# Elavtor.net
KiCad netlist of a schematic drawn in Altium Designer
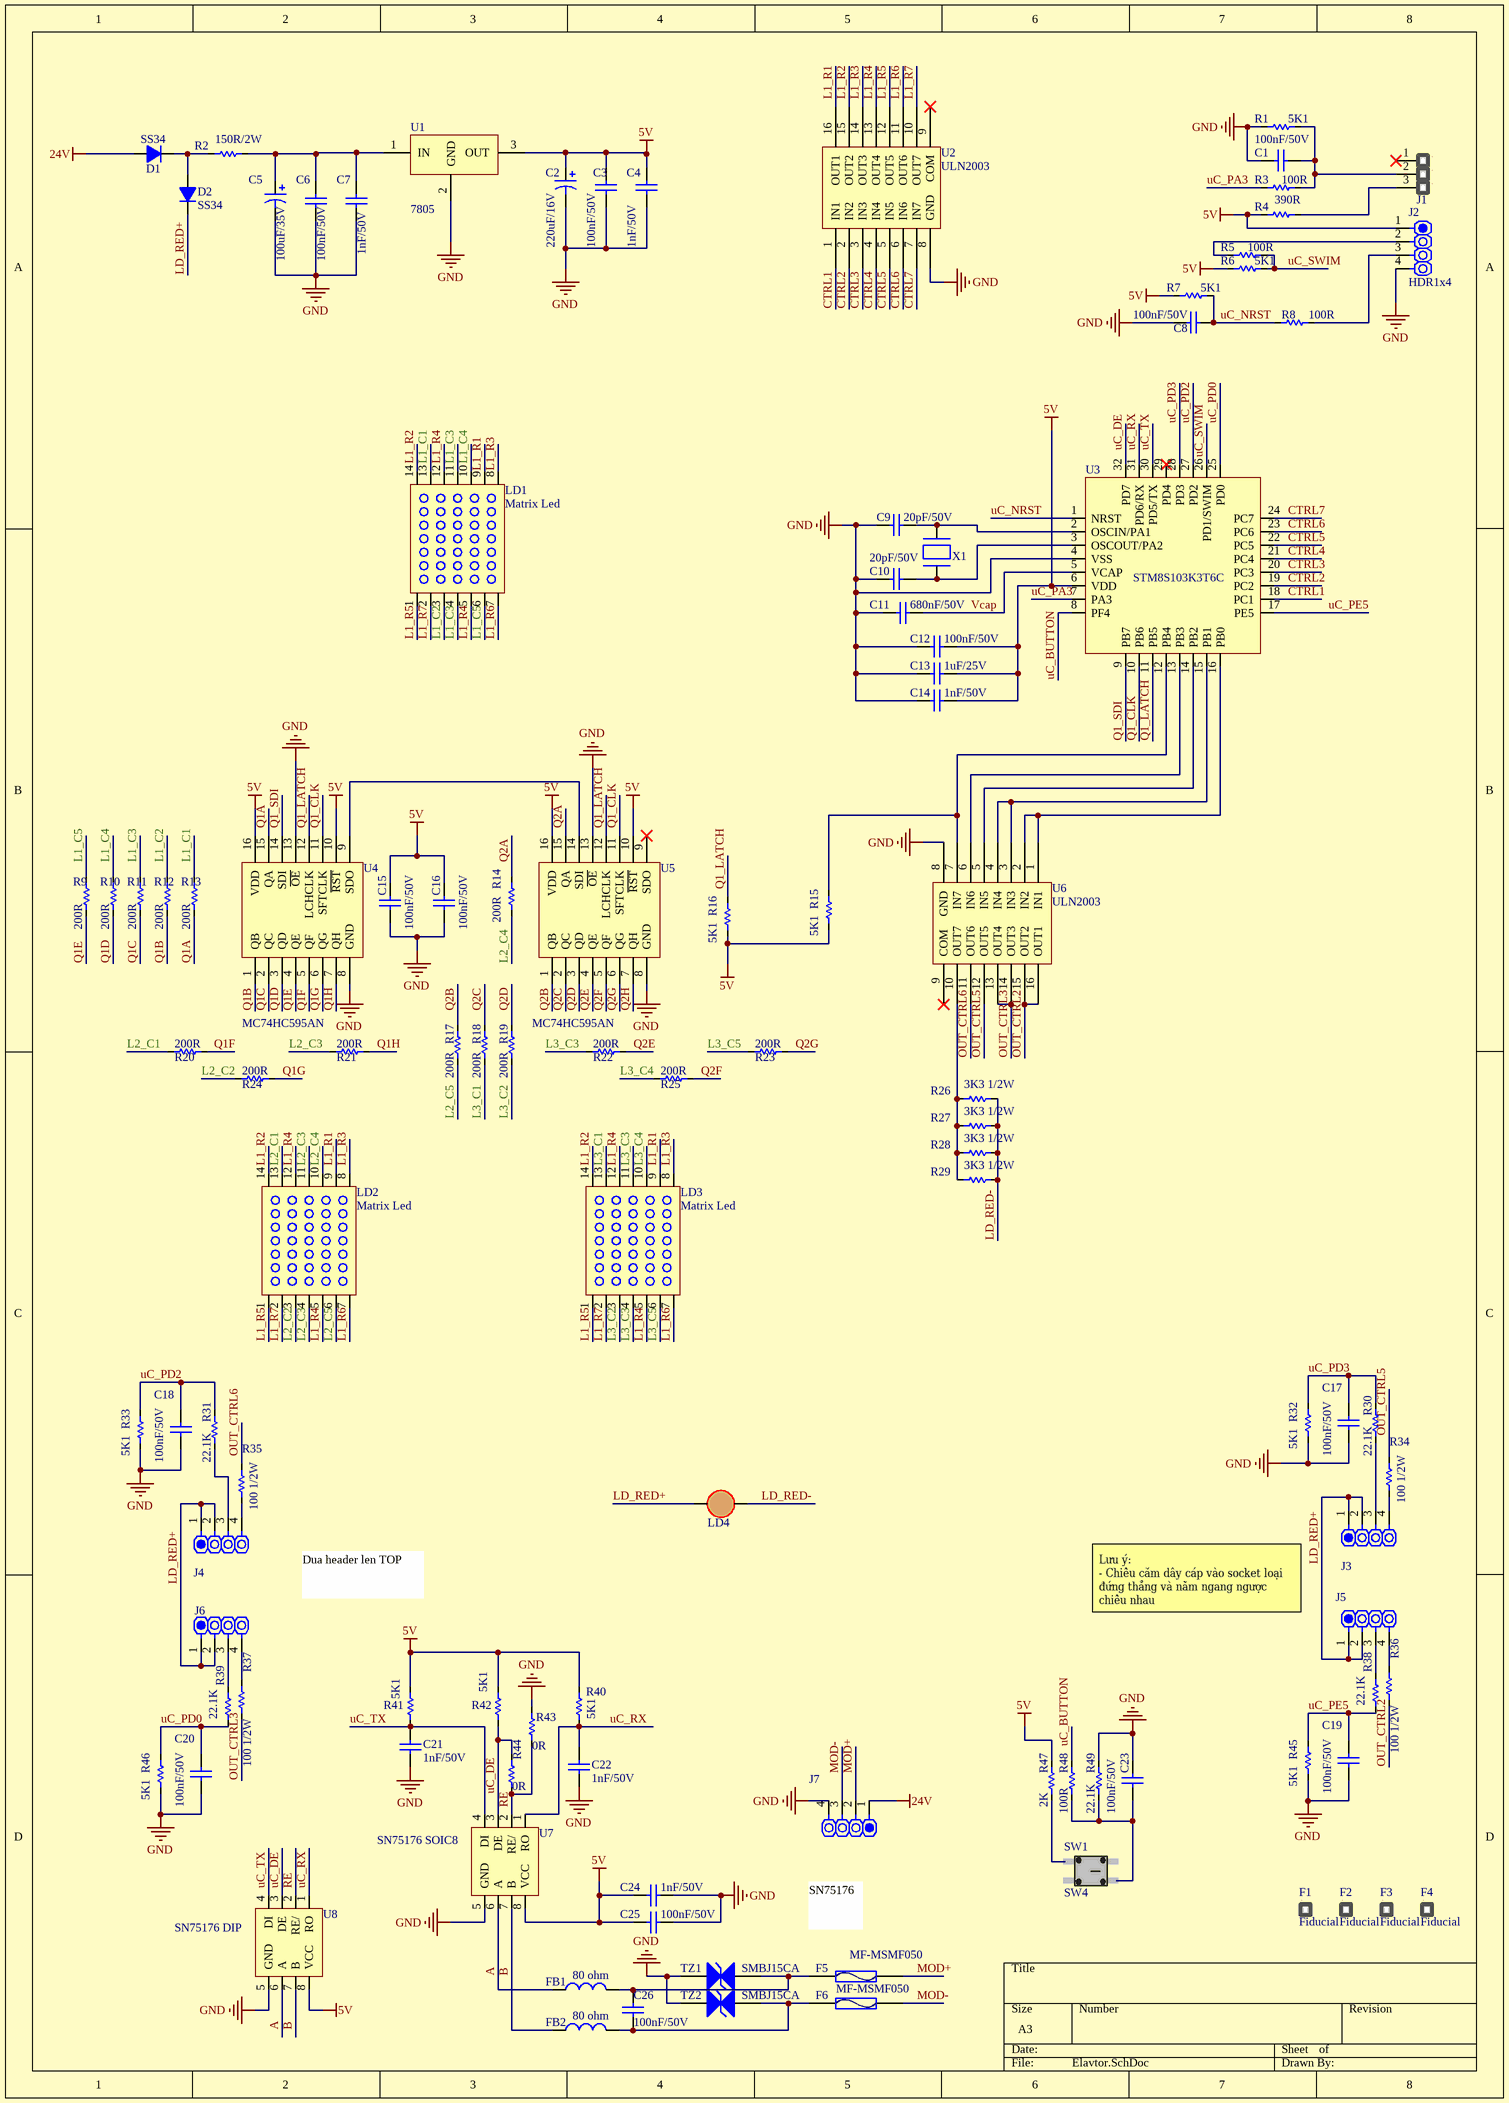
[diagram p0: Elavtor.SchDoc]

(export (version "E")
  (design (tool "Eeschema 10.0.6"))
  (components
    (comp (ref "C1")
      (value "100nF/50V")
      (footprint "FOOTPRINT_SMD:CAPC-0603-1608N")
      (description "CAP CER 100nF 50V 0603")
      (libsource (lib "SCHEMATIC") (part "Cap Ceramic"))
    )
    (comp (ref "C2")
      (value "220uF/16V")
      (footprint "FOOTPRINT_SMD:CAP.SMD_6.3MM")
      (description "Cap Pol 100uF 35V  SMD 6.3x7.7 mm")
      (fields (field (name "PUBLISHER") "Altium Limited"))
      (libsource (lib "SCHEMATIC") (part "Cap Pol 2mm"))
    )
    (comp (ref "C3")
      (value "100nF/50V")
      (footprint "FOOTPRINT_SMD:CAPC-0603-1608N")
      (description "CAP CER 100nF 50V 0603")
      (libsource (lib "SCHEMATIC") (part "Cap Ceramic"))
    )
    (comp (ref "C4")
      (value "1nF/50V")
      (footprint "FOOTPRINT_SMD:CAPC-0603-1608N")
      (description "CAP CER 1nF 50V 0603")
      (libsource (lib "SCHEMATIC") (part "Cap Ceramic"))
    )
    (comp (ref "C5")
      (value "100uF/35V")
      (footprint "FOOTPRINT_SMD:CAP.SMD_6.3MM")
      (description "Cap Pol 100uF 35V  SMD 6.3x7.7 mm")
      (fields (field (name "PUBLISHER") "Altium Limited"))
      (libsource (lib "SCHEMATIC") (part "Cap Pol 2mm"))
    )
    (comp (ref "C6")
      (value "100nF/50V")
      (footprint "FOOTPRINT_SMD:CAPC-0603-1608N")
      (description "CAP CER 100nF 50V 0603")
      (libsource (lib "SCHEMATIC") (part "Cap Ceramic"))
    )
    (comp (ref "C7")
      (value "1nF/50V")
      (footprint "FOOTPRINT_SMD:CAPC-0603-1608N")
      (description "CAP CER 1nF 50V 0603")
      (libsource (lib "SCHEMATIC") (part "Cap Ceramic"))
    )
    (comp (ref "C8")
      (value "100nF/50V")
      (footprint "FOOTPRINT_SMD:CAPC-0603-1608N")
      (description "CAP CER 100nF 50V 0603")
      (libsource (lib "SCHEMATIC") (part "Cap Ceramic"))
    )
    (comp (ref "C9")
      (value "20pF/50V")
      (footprint "FOOTPRINT_SMD:CAPC-0603-1608N")
      (description "CAP CER 20pF 50V 0603")
      (libsource (lib "SCHEMATIC") (part "Cap Ceramic"))
    )
    (comp (ref "C10")
      (value "20pF/50V")
      (footprint "FOOTPRINT_SMD:CAPC-0603-1608N")
      (description "CAP CER 20pF 50V 0603")
      (libsource (lib "SCHEMATIC") (part "Cap Ceramic"))
    )
    (comp (ref "C11")
      (value "680nF/50V")
      (footprint "FOOTPRINT_SMD:CAPC-0603-1608N")
      (description "CAP CER 680nF 50V 0603")
      (libsource (lib "SCHEMATIC") (part "Cap Ceramic"))
    )
    (comp (ref "C12")
      (value "100nF/50V")
      (footprint "FOOTPRINT_SMD:CAPC-0603-1608N")
      (description "CAP CER 100nF 50V 0603")
      (libsource (lib "SCHEMATIC") (part "Cap Ceramic"))
    )
    (comp (ref "C13")
      (value "1uF/25V")
      (footprint "FOOTPRINT_SMD:CAPC-0603-1608N")
      (description "CAP CER 1uF 25V 0603")
      (libsource (lib "SCHEMATIC") (part "Cap Ceramic"))
    )
    (comp (ref "C14")
      (value "1nF/50V")
      (footprint "FOOTPRINT_SMD:CAPC-0603-1608N")
      (description "CAP CER 1nF 50V 0603")
      (libsource (lib "SCHEMATIC") (part "Cap Ceramic"))
    )
    (comp (ref "C15")
      (value "100nF/50V")
      (footprint "FOOTPRINT_SMD:CAPC-0603-1608N")
      (description "CAP CER 100nF 50V 0603")
      (libsource (lib "SCHEMATIC") (part "Cap Ceramic"))
    )
    (comp (ref "C16")
      (value "100nF/50V")
      (footprint "FOOTPRINT_SMD:CAPC-0603-1608N")
      (description "CAP CER 100nF 50V 0603")
      (libsource (lib "SCHEMATIC") (part "Cap Ceramic"))
    )
    (comp (ref "C17")
      (value "100nF/50V")
      (footprint "FOOTPRINT_SMD:CAPC-0603-1608N")
      (description "CAP CER 100nF 50V 0603")
      (libsource (lib "SCHEMATIC") (part "Cap Ceramic"))
    )
    (comp (ref "C18")
      (value "100nF/50V")
      (footprint "FOOTPRINT_SMD:CAPC-0603-1608N")
      (description "CAP CER 100nF 50V 0603")
      (libsource (lib "SCHEMATIC") (part "Cap Ceramic"))
    )
    (comp (ref "C19")
      (value "100nF/50V")
      (footprint "FOOTPRINT_SMD:CAPC-0603-1608N")
      (description "CAP CER 100nF 50V 0603")
      (libsource (lib "SCHEMATIC") (part "Cap Ceramic"))
    )
    (comp (ref "C20")
      (value "100nF/50V")
      (footprint "FOOTPRINT_SMD:CAPC-0603-1608N")
      (description "CAP CER 100nF 50V 0603")
      (libsource (lib "SCHEMATIC") (part "Cap Ceramic"))
    )
    (comp (ref "C21")
      (value "1nF/50V")
      (footprint "FOOTPRINT_SMD:CAPC-0603-1608N")
      (description "CAP CER 1nF 50V 0805")
      (libsource (lib "SCHEMATIC") (part "Cap Ceramic"))
    )
    (comp (ref "C22")
      (value "1nF/50V")
      (footprint "FOOTPRINT_SMD:CAPC-0603-1608N")
      (description "CAP CER 1nF 50V 0603")
      (libsource (lib "SCHEMATIC") (part "Cap Ceramic"))
    )
    (comp (ref "C23")
      (value "100nF/50V")
      (footprint "FOOTPRINT_SMD:CAPC-0603-1608N")
      (description "CAP CER 100nF 50V 0603")
      (libsource (lib "SCHEMATIC") (part "Cap Ceramic"))
    )
    (comp (ref "C24")
      (value "1nF/50V")
      (footprint "FOOTPRINT_SMD:CAPC-0603-1608N")
      (description "CAP CER 1nF 50V 0603")
      (libsource (lib "SCHEMATIC") (part "Cap Ceramic"))
    )
    (comp (ref "C25")
      (value "100nF/50V")
      (footprint "FOOTPRINT_SMD:CAPC-0603-1608N")
      (description "CAP CER 100nF 50V 0603")
      (libsource (lib "SCHEMATIC") (part "Cap Ceramic"))
    )
    (comp (ref "C26")
      (value "100nF/50V")
      (footprint "FOOTPRINT_SMD:CAPC-0603-1608N")
      (description "CAP CER 100nF 50V 0603")
      (libsource (lib "SCHEMATIC") (part "Cap Ceramic"))
    )
    (comp (ref "D1")
      (value "SS34")
      (footprint "FOOTPRINT_SMD:DO-214AC,SMA")
      (description "SS34 SMA")
      (libsource (lib "SCHEMATIC") (part "Diode"))
    )
    (comp (ref "D2")
      (value "SS34")
      (footprint "FOOTPRINT_SMD:DO-214AC,SMA")
      (description "SS34 SMA")
      (libsource (lib "SCHEMATIC") (part "Diode"))
    )
    (comp (ref "F1")
      (value "Fiducial")
      (footprint "FOOTPRINT_SMD:Fiducial")
      (description "SMT Fiducial")
      (libsource (lib "SCHEMATIC") (part "Fiducial"))
    )
    (comp (ref "F2")
      (value "Fiducial")
      (footprint "FOOTPRINT_SMD:Fiducial")
      (description "SMT Fiducial")
      (libsource (lib "SCHEMATIC") (part "Fiducial"))
    )
    (comp (ref "F3")
      (value "Fiducial")
      (footprint "FOOTPRINT_SMD:Fiducial")
      (description "SMT Fiducial")
      (libsource (lib "SCHEMATIC") (part "Fiducial"))
    )
    (comp (ref "F4")
      (value "Fiducial")
      (footprint "FOOTPRINT_SMD:Fiducial")
      (description "SMT Fiducial")
      (libsource (lib "SCHEMATIC") (part "Fiducial"))
    )
    (comp (ref "F5")
      (value "MF-MSMF050")
      (footprint "FOOTPRINT_SMD:FUSE PTC 1812")
      (description "Surface Mount Fuse 1A/250V")
      (fields (field (name "MANUFACTURER") "Bourns Inc"))
      (libsource (lib "SCHEMATIC") (part "Fuse 1"))
    )
    (comp (ref "F6")
      (value "MF-MSMF050")
      (footprint "FOOTPRINT_SMD:FUSE PTC 1812")
      (description "Surface Mount Fuse 1A/250V")
      (fields (field (name "MANUFACTURER") "Bourns Inc"))
      (libsource (lib "SCHEMATIC") (part "Fuse 1"))
    )
    (comp (ref "FB1")
      (value "80 ohm")
      (footprint "L_0805")
      (description "Ferrite Bead 80 Ohm @100MHz nductor 0805")
      (libsource (lib "SCHEMATIC") (part "Inductor"))
    )
    (comp (ref "FB2")
      (value "80 ohm")
      (footprint "L_0805")
      (description "Ferrite Bead 80 Ohm @100MHz nductor 0805")
      (libsource (lib "SCHEMATIC") (part "Inductor"))
    )
    (comp (ref "J1")
      (value "HDR1x3")
      (footprint "FOOTPRINT_TH:HDR1X3")
      (description "2.54mm 3x1 Single Male Pin Header")
      (libsource (lib "SCHEMATIC") (part "HDR 1x3"))
    )
    (comp (ref "J2")
      (value "HDR1x4")
      (footprint "FOOTPRINT_TH:HDR1X4")
      (description "2.54mm 4x1 Single Male Pin Header")
      (fields (field (name "MANUFACTURER") "Taiwan") (field (name "PART NUMBER") "HEADER1X4"))
      (libsource (lib "SCHEMATIC") (part "HDR 1x4"))
    )
    (comp (ref "J3")
      (value "HDR1x4")
      (footprint "FOOTPRINT_TH:Hdr1x4 R Box")
      (description "5.08mm 4x1 Single Male RIght pin Header")
      (fields (field (name "MANUFACTURER") "Taiwan") (field (name "PART NUMBER") "HEADER1X4"))
      (libsource (lib "SCHEMATIC") (part "HDR 1x4"))
    )
    (comp (ref "J4")
      (value "HDR1x4")
      (footprint "FOOTPRINT_TH:Hdr1x4 R Box")
      (description "5.08mm 4x1 Single Male RIght pin Header")
      (fields (field (name "MANUFACTURER") "Taiwan") (field (name "PART NUMBER") "HEADER1X4"))
      (libsource (lib "SCHEMATIC") (part "HDR 1x4"))
    )
    (comp (ref "J5")
      (value "HDR1x4")
      (footprint "FOOTPRINT_TH:Hdr1x4 R Box")
      (description "5.08mm 4x1 Single Male RIght pin Header")
      (fields (field (name "MANUFACTURER") "Taiwan") (field (name "PART NUMBER") "HEADER1X4"))
      (libsource (lib "SCHEMATIC") (part "HDR 1x4"))
    )
    (comp (ref "J6")
      (value "HDR1x4")
      (footprint "FOOTPRINT_TH:Hdr1x4 R Box")
      (description "5.08mm 4x1 Single Male RIght pin Header")
      (fields (field (name "MANUFACTURER") "Taiwan") (field (name "PART NUMBER") "HEADER1X4"))
      (libsource (lib "SCHEMATIC") (part "HDR 1x4"))
    )
    (comp (ref "J7")
      (value "HDR1x4")
      (footprint "FOOTPRINT_TH:Hdr1x4 R Box")
      (description "5.08mm 4x1 Single Male RIght pin Header")
      (fields (field (name "MANUFACTURER") "Taiwan") (field (name "PART NUMBER") "HEADER1X4"))
      (libsource (lib "SCHEMATIC") (part "HDR 1x4"))
    )
    (comp (ref "LD1")
      (value "Matrix Led")
      (footprint "FOOTPRINT_TH:LED_Matrix 5*7")
      (description "Matrix Led 5x7")
      (libsource (lib "SCHEMATIC") (part "Matrix Led 5x7"))
    )
    (comp (ref "LD2")
      (value "Matrix Led")
      (footprint "FOOTPRINT_TH:LED_Matrix 5*7")
      (description "Matrix Led 5x7")
      (libsource (lib "SCHEMATIC") (part "Matrix Led 5x7"))
    )
    (comp (ref "LD3")
      (value "Matrix Led")
      (footprint "FOOTPRINT_TH:LED_Matrix 5*7")
      (description "Matrix Led 5x7")
      (libsource (lib "SCHEMATIC") (part "Matrix Led 5x7"))
    )
    (comp (ref "LD4")
      (value "LED TH 33x22 mm")
      (footprint "FOOTPRINT_TH:LED. 33x22 mm")
      (fields
        (field (name "MANUFACTURER") "Harvatek Technologies")
        (field (name "PART NUMBER") "HT17-2102SURC")
      )
      (libsource (lib "SCHEMATIC") (part "LED SINGLE"))
    )
    (comp (ref "R1")
      (value "5K1")
      (footprint "FOOTPRINT_SMD:R.SMD_0603")
      (description "RES SMD 5K1 OHM 5% 1/8W 0603")
      (fields (field (name "MANUFACTURER") "SUPEROHM") (field (name "PART NUMBER") "RR1608(0603)L102JT"))
      (libsource (lib "SCHEMATIC") (part "Resistor 1/4W"))
    )
    (comp (ref "R2")
      (value "150R/2W")
      (footprint "FOOTPRINT_TH:Resistor 1.5-2w")
      (description "RES SMD 150R OHM 5% 2W TH")
      (fields (field (name "MANUFACTURER") "SUPEROHM") (field (name "PART NUMBER") "RR1608(0603)L102JT"))
      (libsource (lib "SCHEMATIC") (part "Resistor 1/4W"))
    )
    (comp (ref "R3")
      (value "100R")
      (footprint "FOOTPRINT_SMD:R.SMD_0603")
      (description "RES SMD 100R OHM 1% 1/8W 0603")
      (fields (field (name "MANUFACTURER") "SUPEROHM") (field (name "PART NUMBER") "RR1608(0603)L102JT"))
      (libsource (lib "SCHEMATIC") (part "Resistor 1/4W"))
    )
    (comp (ref "R4")
      (value "390R")
      (footprint "FOOTPRINT_SMD:R.SMD_0603")
      (description "RES SMD 390R OHM 5% 1/8W 0603")
      (fields (field (name "MANUFACTURER") "SUPEROHM") (field (name "PART NUMBER") "RR1608(0603)L102JT"))
      (libsource (lib "SCHEMATIC") (part "Resistor 1/4W"))
    )
    (comp (ref "R5")
      (value "100R")
      (footprint "FOOTPRINT_SMD:R.SMD_0603")
      (description "RES SMD 100R OHM 1% 1/8W 0603")
      (fields (field (name "MANUFACTURER") "SUPEROHM") (field (name "PART NUMBER") "RR1608(0603)L102JT"))
      (libsource (lib "SCHEMATIC") (part "Resistor 1/4W"))
    )
    (comp (ref "R6")
      (value "5K1")
      (footprint "FOOTPRINT_SMD:R.SMD_0603")
      (description "RES SMD 5K1 OHM 5% 1/8W 0603")
      (fields (field (name "MANUFACTURER") "SUPEROHM") (field (name "PART NUMBER") "RR1608(0603)L102JT"))
      (libsource (lib "SCHEMATIC") (part "Resistor 1/4W"))
    )
    (comp (ref "R7")
      (value "5K1")
      (footprint "FOOTPRINT_SMD:R.SMD_0603")
      (description "RES SMD 5K1 OHM 5% 1/8W 0603")
      (fields (field (name "MANUFACTURER") "SUPEROHM") (field (name "PART NUMBER") "RR1608(0603)L102JT"))
      (libsource (lib "SCHEMATIC") (part "Resistor 1/4W"))
    )
    (comp (ref "R8")
      (value "100R")
      (footprint "FOOTPRINT_SMD:R.SMD_0603")
      (description "RES SMD 100R OHM 1% 1/10W 0603")
      (fields (field (name "MANUFACTURER") "SUPEROHM") (field (name "PART NUMBER") "RR1608(0603)L102JT"))
      (libsource (lib "SCHEMATIC") (part "Resistor 1/4W"))
    )
    (comp (ref "R9")
      (value "200R")
      (footprint "FOOTPRINT_SMD:R.SMD_0603")
      (description "RES SMD 200R OHM 5% 180W 0603")
      (fields (field (name "MANUFACTURER") "SUPEROHM") (field (name "PART NUMBER") "RR1608(0603)L102JT"))
      (libsource (lib "SCHEMATIC") (part "Resistor 1/4W"))
    )
    (comp (ref "R10")
      (value "200R")
      (footprint "FOOTPRINT_SMD:R.SMD_0603")
      (description "RES SMD 200R OHM 5% 180W 0603")
      (fields (field (name "MANUFACTURER") "SUPEROHM") (field (name "PART NUMBER") "RR1608(0603)L102JT"))
      (libsource (lib "SCHEMATIC") (part "Resistor 1/4W"))
    )
    (comp (ref "R11")
      (value "200R")
      (footprint "FOOTPRINT_SMD:R.SMD_0603")
      (description "RES SMD 200R OHM 5% 180W 0603")
      (fields (field (name "MANUFACTURER") "SUPEROHM") (field (name "PART NUMBER") "RR1608(0603)L102JT"))
      (libsource (lib "SCHEMATIC") (part "Resistor 1/4W"))
    )
    (comp (ref "R12")
      (value "200R")
      (footprint "FOOTPRINT_SMD:R.SMD_0603")
      (description "RES SMD 200R OHM 5% 180W 0603")
      (fields (field (name "MANUFACTURER") "SUPEROHM") (field (name "PART NUMBER") "RR1608(0603)L102JT"))
      (libsource (lib "SCHEMATIC") (part "Resistor 1/4W"))
    )
    (comp (ref "R13")
      (value "200R")
      (footprint "FOOTPRINT_SMD:R.SMD_0603")
      (description "RES SMD 200R OHM 5% 180W 0603")
      (fields (field (name "MANUFACTURER") "SUPEROHM") (field (name "PART NUMBER") "RR1608(0603)L102JT"))
      (libsource (lib "SCHEMATIC") (part "Resistor 1/4W"))
    )
    (comp (ref "R14")
      (value "200R")
      (footprint "FOOTPRINT_SMD:R.SMD_0603")
      (description "RES SMD 200R OHM 5% 180W 0603")
      (fields (field (name "MANUFACTURER") "SUPEROHM") (field (name "PART NUMBER") "RR1608(0603)L102JT"))
      (libsource (lib "SCHEMATIC") (part "Resistor 1/4W"))
    )
    (comp (ref "R15")
      (value "5K1")
      (footprint "FOOTPRINT_SMD:R.SMD_0603")
      (description "RES SMD 5K1 OHM 5% 1/8W 0603")
      (fields (field (name "MANUFACTURER") "SUPEROHM") (field (name "PART NUMBER") "RR1608(0603)L102JT"))
      (libsource (lib "SCHEMATIC") (part "Resistor 1/4W"))
    )
    (comp (ref "R16")
      (value "5K1")
      (footprint "FOOTPRINT_SMD:R.SMD_0603")
      (description "RES SMD 5K1 OHM 5% 1/8W 0603")
      (fields (field (name "MANUFACTURER") "SUPEROHM") (field (name "PART NUMBER") "RR1608(0603)L102JT"))
      (libsource (lib "SCHEMATIC") (part "Resistor 1/4W"))
    )
    (comp (ref "R17")
      (value "200R")
      (footprint "FOOTPRINT_SMD:R.SMD_0603")
      (description "RES SMD 200R OHM 5% 180W 0603")
      (fields (field (name "MANUFACTURER") "SUPEROHM") (field (name "PART NUMBER") "RR1608(0603)L102JT"))
      (libsource (lib "SCHEMATIC") (part "Resistor 1/4W"))
    )
    (comp (ref "R18")
      (value "200R")
      (footprint "FOOTPRINT_SMD:R.SMD_0603")
      (description "RES SMD 200R OHM 5% 180W 0603")
      (fields (field (name "MANUFACTURER") "SUPEROHM") (field (name "PART NUMBER") "RR1608(0603)L102JT"))
      (libsource (lib "SCHEMATIC") (part "Resistor 1/4W"))
    )
    (comp (ref "R19")
      (value "200R")
      (footprint "FOOTPRINT_SMD:R.SMD_0603")
      (description "RES SMD 200R OHM 5% 180W 0603")
      (fields (field (name "MANUFACTURER") "SUPEROHM") (field (name "PART NUMBER") "RR1608(0603)L102JT"))
      (libsource (lib "SCHEMATIC") (part "Resistor 1/4W"))
    )
    (comp (ref "R20")
      (value "200R")
      (footprint "FOOTPRINT_SMD:R.SMD_0603")
      (description "RES SMD 200R OHM 5% 180W 0603")
      (fields (field (name "MANUFACTURER") "SUPEROHM") (field (name "PART NUMBER") "RR1608(0603)L102JT"))
      (libsource (lib "SCHEMATIC") (part "Resistor 1/4W"))
    )
    (comp (ref "R21")
      (value "200R")
      (footprint "FOOTPRINT_SMD:R.SMD_0603")
      (description "RES SMD 200R OHM 5% 180W 0603")
      (fields (field (name "MANUFACTURER") "SUPEROHM") (field (name "PART NUMBER") "RR1608(0603)L102JT"))
      (libsource (lib "SCHEMATIC") (part "Resistor 1/4W"))
    )
    (comp (ref "R22")
      (value "200R")
      (footprint "FOOTPRINT_SMD:R.SMD_0603")
      (description "RES SMD 200R OHM 5% 180W 0603")
      (fields (field (name "MANUFACTURER") "SUPEROHM") (field (name "PART NUMBER") "RR1608(0603)L102JT"))
      (libsource (lib "SCHEMATIC") (part "Resistor 1/4W"))
    )
    (comp (ref "R23")
      (value "200R")
      (footprint "FOOTPRINT_SMD:R.SMD_0603")
      (description "RES SMD 200R OHM 5% 180W 0603")
      (fields (field (name "MANUFACTURER") "SUPEROHM") (field (name "PART NUMBER") "RR1608(0603)L102JT"))
      (libsource (lib "SCHEMATIC") (part "Resistor 1/4W"))
    )
    (comp (ref "R24")
      (value "200R")
      (footprint "FOOTPRINT_SMD:R.SMD_0603")
      (description "RES SMD 200R OHM 5% 180W 0603")
      (fields (field (name "MANUFACTURER") "SUPEROHM") (field (name "PART NUMBER") "RR1608(0603)L102JT"))
      (libsource (lib "SCHEMATIC") (part "Resistor 1/4W"))
    )
    (comp (ref "R25")
      (value "200R")
      (footprint "FOOTPRINT_SMD:R.SMD_0603")
      (description "RES SMD 200R OHM 5% 180W 0603")
      (fields (field (name "MANUFACTURER") "SUPEROHM") (field (name "PART NUMBER") "RR1608(0603)L102JT"))
      (libsource (lib "SCHEMATIC") (part "Resistor 1/4W"))
    )
    (comp (ref "R26")
      (value "3K3 1/2W")
      (footprint "FOOTPRINT_SMD:R.SMD_1210")
      (description "RES SMD 3K3 OHM 5% 1/2W 1210")
      (fields (field (name "MANUFACTURER") "SUPEROHM") (field (name "PART NUMBER") "RR1608(0603)L102JT"))
      (libsource (lib "SCHEMATIC") (part "Resistor 1/4W"))
    )
    (comp (ref "R27")
      (value "3K3 1/2W")
      (footprint "FOOTPRINT_SMD:R.SMD_1210")
      (description "RES SMD 3K3 OHM 5% 1/2W 1210")
      (fields (field (name "MANUFACTURER") "SUPEROHM") (field (name "PART NUMBER") "RR1608(0603)L102JT"))
      (libsource (lib "SCHEMATIC") (part "Resistor 1/4W"))
    )
    (comp (ref "R28")
      (value "3K3 1/2W")
      (footprint "FOOTPRINT_SMD:R.SMD_1210")
      (description "RES SMD 3K3 OHM 5% 1/2W 1210")
      (fields (field (name "MANUFACTURER") "SUPEROHM") (field (name "PART NUMBER") "RR1608(0603)L102JT"))
      (libsource (lib "SCHEMATIC") (part "Resistor 1/4W"))
    )
    (comp (ref "R29")
      (value "3K3 1/2W")
      (footprint "FOOTPRINT_SMD:R.SMD_1210")
      (description "RES SMD 3K3 OHM 5% 1/2W 1210")
      (fields (field (name "MANUFACTURER") "SUPEROHM") (field (name "PART NUMBER") "RR1608(0603)L102JT"))
      (libsource (lib "SCHEMATIC") (part "Resistor 1/4W"))
    )
    (comp (ref "R30")
      (value "22.1K")
      (footprint "FOOTPRINT_SMD:R.SMD_0603")
      (description "RES SMD 22.1K OHM 5% 1/8W 0603")
      (fields (field (name "MANUFACTURER") "SUPEROHM") (field (name "PART NUMBER") "RR1608(0603)L102JT"))
      (libsource (lib "SCHEMATIC") (part "Resistor 1/4W"))
    )
    (comp (ref "R31")
      (value "22.1K")
      (footprint "FOOTPRINT_SMD:R.SMD_0603")
      (description "RES SMD 22.1K OHM 5% 1/8W 0603")
      (fields (field (name "MANUFACTURER") "SUPEROHM") (field (name "PART NUMBER") "RR1608(0603)L102JT"))
      (libsource (lib "SCHEMATIC") (part "Resistor 1/4W"))
    )
    (comp (ref "R32")
      (value "5K1")
      (footprint "FOOTPRINT_SMD:R.SMD_0603")
      (description "RES SMD 5K1 OHM 5% 1/8W 0603")
      (fields (field (name "MANUFACTURER") "SUPEROHM") (field (name "PART NUMBER") "RR1608(0603)L102JT"))
      (libsource (lib "SCHEMATIC") (part "Resistor 1/4W"))
    )
    (comp (ref "R33")
      (value "5K1")
      (footprint "FOOTPRINT_SMD:R.SMD_0603")
      (description "RES SMD 5K1 OHM 5% 1/8W 0603")
      (fields (field (name "MANUFACTURER") "SUPEROHM") (field (name "PART NUMBER") "RR1608(0603)L102JT"))
      (libsource (lib "SCHEMATIC") (part "Resistor 1/4W"))
    )
    (comp (ref "R34")
      (value "100 1/2W")
      (footprint "FOOTPRINT_SMD:R.SMD_1210")
      (description "RES SMD 100 OHM 5% 1/2W 1210")
      (fields (field (name "MANUFACTURER") "SUPEROHM") (field (name "PART NUMBER") "RR1608(0603)L102JT"))
      (libsource (lib "SCHEMATIC") (part "Resistor 1/4W"))
    )
    (comp (ref "R35")
      (value "100 1/2W")
      (footprint "FOOTPRINT_SMD:R.SMD_1210")
      (description "RES SMD 100 OHM 5% 1/2W 1210")
      (fields (field (name "MANUFACTURER") "SUPEROHM") (field (name "PART NUMBER") "RR1608(0603)L102JT"))
      (libsource (lib "SCHEMATIC") (part "Resistor 1/4W"))
    )
    (comp (ref "R36")
      (value "100 1/2W")
      (footprint "FOOTPRINT_SMD:R.SMD_1210")
      (description "RES SMD 100 OHM 5% 1/2W 1210")
      (fields (field (name "MANUFACTURER") "SUPEROHM") (field (name "PART NUMBER") "RR1608(0603)L102JT"))
      (libsource (lib "SCHEMATIC") (part "Resistor 1/4W"))
    )
    (comp (ref "R37")
      (value "100 1/2W")
      (footprint "FOOTPRINT_SMD:R.SMD_1210")
      (description "RES SMD 100 OHM 5% 1/2W 1210")
      (fields (field (name "MANUFACTURER") "SUPEROHM") (field (name "PART NUMBER") "RR1608(0603)L102JT"))
      (libsource (lib "SCHEMATIC") (part "Resistor 1/4W"))
    )
    (comp (ref "R38")
      (value "22.1K")
      (footprint "FOOTPRINT_SMD:R.SMD_0603")
      (description "RES SMD 22.1K OHM 5% 1/8W 0603")
      (fields (field (name "MANUFACTURER") "SUPEROHM") (field (name "PART NUMBER") "RR1608(0603)L102JT"))
      (libsource (lib "SCHEMATIC") (part "Resistor 1/4W"))
    )
    (comp (ref "R39")
      (value "22.1K")
      (footprint "FOOTPRINT_SMD:R.SMD_0603")
      (description "RES SMD 22.1K OHM 5% 1/8W 0603")
      (fields (field (name "MANUFACTURER") "SUPEROHM") (field (name "PART NUMBER") "RR1608(0603)L102JT"))
      (libsource (lib "SCHEMATIC") (part "Resistor 1/4W"))
    )
    (comp (ref "R40")
      (value "5K1")
      (footprint "FOOTPRINT_SMD:R.SMD_0603")
      (description "RES SMD 5K1 OHM 5% 1/8W 0603")
      (fields (field (name "MANUFACTURER") "SUPEROHM") (field (name "PART NUMBER") "RR1608(0603)L102JT"))
      (libsource (lib "SCHEMATIC") (part "Resistor 1/4W"))
    )
    (comp (ref "R41")
      (value "5K1")
      (footprint "FOOTPRINT_SMD:R.SMD_0603")
      (description "RES SMD 5K1 OHM 5% 1/8W 0603")
      (fields (field (name "MANUFACTURER") "SUPEROHM") (field (name "PART NUMBER") "RR1608(0603)L102JT"))
      (libsource (lib "SCHEMATIC") (part "Resistor 1/4W"))
    )
    (comp (ref "R42")
      (value "5K1")
      (footprint "FOOTPRINT_SMD:R.SMD_0603")
      (description "RES SMD 5K1 OHM 5% 1/8W 0603")
      (fields (field (name "MANUFACTURER") "SUPEROHM") (field (name "PART NUMBER") "RR1608(0603)L102JT"))
      (libsource (lib "SCHEMATIC") (part "Resistor 1/4W"))
    )
    (comp (ref "R43")
      (value "0R")
      (footprint "FOOTPRINT_SMD:R.SMD_0603")
      (description "RES SMD 0R OHM 1% 1/10W 0603")
      (fields (field (name "MANUFACTURER") "SUPEROHM") (field (name "PART NUMBER") "RR1608(0603)L102JT"))
      (libsource (lib "SCHEMATIC") (part "Resistor 1/4W"))
    )
    (comp (ref "R44")
      (value "0R")
      (footprint "FOOTPRINT_SMD:R.SMD_0603")
      (description "RES SMD 0R OHM 1% 1/10W 0603")
      (fields (field (name "MANUFACTURER") "SUPEROHM") (field (name "PART NUMBER") "RR1608(0603)L102JT"))
      (libsource (lib "SCHEMATIC") (part "Resistor 1/4W"))
    )
    (comp (ref "R45")
      (value "5K1")
      (footprint "FOOTPRINT_SMD:R.SMD_0603")
      (description "RES SMD 5K1 OHM 5% 1/8W 0603")
      (fields (field (name "MANUFACTURER") "SUPEROHM") (field (name "PART NUMBER") "RR1608(0603)L102JT"))
      (libsource (lib "SCHEMATIC") (part "Resistor 1/4W"))
    )
    (comp (ref "R46")
      (value "5K1")
      (footprint "FOOTPRINT_SMD:R.SMD_0603")
      (description "RES SMD 5K1 OHM 5% 1/8W 0603")
      (fields (field (name "MANUFACTURER") "SUPEROHM") (field (name "PART NUMBER") "RR1608(0603)L102JT"))
      (libsource (lib "SCHEMATIC") (part "Resistor 1/4W"))
    )
    (comp (ref "R47")
      (value "2K")
      (footprint "FOOTPRINT_SMD:R.SMD_0603")
      (description "RES SMD 2K OHM 5% 1/8W 0603")
      (fields (field (name "MANUFACTURER") "SUPEROHM") (field (name "PART NUMBER") "RR1608(0603)L102JT"))
      (libsource (lib "SCHEMATIC") (part "Resistor 1/4W"))
    )
    (comp (ref "R48")
      (value "100R")
      (footprint "FOOTPRINT_SMD:R.SMD_0603")
      (description "RES SMD 100R OHM 1% 1/10W 0603")
      (fields (field (name "MANUFACTURER") "SUPEROHM") (field (name "PART NUMBER") "RR1608(0603)L102JT"))
      (libsource (lib "SCHEMATIC") (part "Resistor 1/4W"))
    )
    (comp (ref "R49")
      (value "22.1K")
      (footprint "FOOTPRINT_SMD:R.SMD_0603")
      (description "RES SMD 22.1K OHM 5% 1/8W 0603")
      (fields (field (name "MANUFACTURER") "SUPEROHM") (field (name "PART NUMBER") "RR1608(0603)L102JT"))
      (libsource (lib "SCHEMATIC") (part "Resistor 1/4W"))
    )
    (comp (ref "SW1")
      (value "SW4")
      (footprint "FOOTPRINT_TH:SW4 SMALL")
      (description "Tact Switch 6x6x5 Black")
      (fields (field (name "PART NUMBER") "KAN0611-0501B"))
      (libsource (lib "SCHEMATIC") (part "SW4"))
    )
    (comp (ref "TZ1")
      (value "SMBJ15CA")
      (footprint "FOOTPRINT_SMD:DO-214AA,SMB")
      (fields (field (name "MANUFACTURER") "ON Semi"))
      (libsource (lib "Schematic") (part "TVS"))
    )
    (comp (ref "TZ2")
      (value "SMBJ15CA")
      (footprint "FOOTPRINT_SMD:DO-214AA,SMB")
      (fields (field (name "MANUFACTURER") "ON Semi"))
      (libsource (lib "Schematic") (part "TVS"))
    )
    (comp (ref "U1")
      (value "7805")
      (footprint "FOOTPRINT_SMD:TO-252")
      (description "LM7805 SMD TO-252")
      (libsource (lib "SCHEMATIC") (part "78XX"))
    )
    (comp (ref "U2")
      (value "ULN2003")
      (footprint "FOOTPRINT_SMD:SOIC16_150_N")
      (description "High-Current Darlington Transistor Arrays")
      (fields (field (name "MANUFACTURER") "Texas instruments"))
      (libsource (lib "") (part "ULN2003_1"))
    )
    (comp (ref "U3")
      (value "STM8S103K3T6C")
      (footprint "FOOTPRINT_SMD:LQFP32")
      (description "16 MHz STM8S 8-bit MCU, up to 8 Kbytes Flash, data\r\nEEPROM,10-bit ADC, 3 timers, UART, SPI, I²C")
      (libsource (lib "SCHEMATIC") (part "STM8S103K3T6C"))
    )
    (comp (ref "U4")
      (value "MC74HC595AN")
      (footprint "FOOTPRINT_SMD:SOIC16_150_N")
      (description "8-Bit Serial-Input/Serial or Prallel-Output Shift Register with Latched 3-State Outputs")
      (fields (field (name "PUBLISHER") "Altium Limited"))
      (libsource (lib "SCHEMATIC") (part "MC74HC595AN"))
    )
    (comp (ref "U5")
      (value "MC74HC595AN")
      (footprint "FOOTPRINT_SMD:SOIC16_150_N")
      (description "8-Bit Serial-Input/Serial or Prallel-Output Shift Register with Latched 3-State Outputs")
      (fields (field (name "PUBLISHER") "Altium Limited"))
      (libsource (lib "SCHEMATIC") (part "MC74HC595AN"))
    )
    (comp (ref "U6")
      (value "ULN2003")
      (footprint "FOOTPRINT_SMD:SOIC16_150_N")
      (description "High-Current Darlington Transistor Arrays")
      (fields (field (name "MANUFACTURER") "Texas instruments"))
      (libsource (lib "SCHEMATIC") (part "ULN2003"))
    )
    (comp (ref "U7")
      (value "SN75176 SOIC8")
      (footprint "FOOTPRINT_SMD:SOIC8 - JEDEC")
      (description "SN65HVD3082E")
      (fields (field (name "PART NUMBER") "SP485"))
      (libsource (lib "SCHEMATIC") (part "RS485"))
    )
    (comp (ref "U8")
      (value "SN75176 DIP")
      (footprint "FOOTPRINT_TH:DIP8/W0.3")
      (description "SOCKET DIP 8")
      (fields (field (name "PART NUMBER") "SP485"))
      (libsource (lib "SCHEMATIC") (part "RS485"))
    )
    (comp (ref "X1")
      (value "16MHz")
      (footprint "FOOTPRINT_TH:CRYSTAL")
      (description "CRYSTAL 16MHz 7PF SMD")
      (libsource (lib "SCHEMATIC") (part "CRYSTAL"))
    )
  )
  (nets
    (net (code "1") (name "/A") (class "Default")
      (node (ref "FB1") (pin "1") (pinfunction "1_1") (pintype "passive"))
      (node (ref "U7") (pin "6") (pinfunction "A_6") (pintype "passive"))
      (node (ref "U8") (pin "6") (pinfunction "A_6") (pintype "passive"))
    )
    (net (code "2") (name "/B") (class "Default")
      (node (ref "FB2") (pin "1") (pinfunction "1_1") (pintype "passive"))
      (node (ref "U7") (pin "7") (pinfunction "B_7") (pintype "passive"))
      (node (ref "U8") (pin "7") (pinfunction "B_7") (pintype "passive"))
    )
    (net (code "3") (name "/CTRL1") (class "Default")
      (node (ref "U2") (pin "1") (pinfunction "IN1_1") (pintype "passive"))
      (node (ref "U3") (pin "18") (pinfunction "PC1_18") (pintype "passive"))
    )
    (net (code "4") (name "/CTRL2") (class "Default")
      (node (ref "U2") (pin "2") (pinfunction "IN2_2") (pintype "passive"))
      (node (ref "U3") (pin "19") (pinfunction "PC2_19") (pintype "passive"))
    )
    (net (code "5") (name "/CTRL3") (class "Default")
      (node (ref "U2") (pin "3") (pinfunction "IN3_3") (pintype "passive"))
      (node (ref "U3") (pin "20") (pinfunction "PC3_20") (pintype "passive"))
    )
    (net (code "6") (name "/CTRL4") (class "Default")
      (node (ref "U2") (pin "4") (pinfunction "IN4_4") (pintype "passive"))
      (node (ref "U3") (pin "21") (pinfunction "PC4_21") (pintype "passive"))
    )
    (net (code "7") (name "/CTRL5") (class "Default")
      (node (ref "U2") (pin "5") (pinfunction "IN5_5") (pintype "passive"))
      (node (ref "U3") (pin "22") (pinfunction "PC5_22") (pintype "passive"))
    )
    (net (code "8") (name "/CTRL6") (class "Default")
      (node (ref "U2") (pin "6") (pinfunction "IN6_6") (pintype "passive"))
      (node (ref "U3") (pin "23") (pinfunction "PC6_23") (pintype "passive"))
    )
    (net (code "9") (name "/CTRL7") (class "Default")
      (node (ref "U2") (pin "7") (pinfunction "IN7_7") (pintype "passive"))
      (node (ref "U3") (pin "24") (pinfunction "PC7_24") (pintype "passive"))
    )
    (net (code "10") (name "/L1_C1") (class "Default")
      (node (ref "LD1") (pin "13") (pinfunction "13_13") (pintype "passive"))
      (node (ref "R13") (pin "2") (pinfunction "2_2") (pintype "passive"))
    )
    (net (code "11") (name "/L1_C2") (class "Default")
      (node (ref "LD1") (pin "3") (pinfunction "3_3") (pintype "passive"))
      (node (ref "R12") (pin "2") (pinfunction "2_2") (pintype "passive"))
    )
    (net (code "12") (name "/L1_C3") (class "Default")
      (node (ref "LD1") (pin "11") (pinfunction "11_11") (pintype "passive"))
      (node (ref "LD1") (pin "4") (pinfunction "4_4") (pintype "passive"))
      (node (ref "R11") (pin "2") (pinfunction "2_2") (pintype "passive"))
    )
    (net (code "13") (name "/L1_C4") (class "Default")
      (node (ref "LD1") (pin "10") (pinfunction "10_10") (pintype "passive"))
      (node (ref "R10") (pin "2") (pinfunction "2_2") (pintype "passive"))
    )
    (net (code "14") (name "/L1_C5") (class "Default")
      (node (ref "LD1") (pin "6") (pinfunction "6_6") (pintype "passive"))
      (node (ref "R9") (pin "2") (pinfunction "2_2") (pintype "passive"))
    )
    (net (code "15") (name "/L1_R1") (class "Default")
      (node (ref "LD1") (pin "9") (pinfunction "9_9") (pintype "passive"))
      (node (ref "LD2") (pin "9") (pinfunction "9_9") (pintype "passive"))
      (node (ref "LD3") (pin "9") (pinfunction "9_9") (pintype "passive"))
      (node (ref "U2") (pin "16") (pinfunction "OUT1_16") (pintype "passive"))
    )
    (net (code "16") (name "/L1_R2") (class "Default")
      (node (ref "LD1") (pin "14") (pinfunction "14_14") (pintype "passive"))
      (node (ref "LD2") (pin "14") (pinfunction "14_14") (pintype "passive"))
      (node (ref "LD3") (pin "14") (pinfunction "14_14") (pintype "passive"))
      (node (ref "U2") (pin "15") (pinfunction "OUT2_15") (pintype "passive"))
    )
    (net (code "17") (name "/L1_R3") (class "Default")
      (node (ref "LD1") (pin "8") (pinfunction "8_8") (pintype "passive"))
      (node (ref "LD2") (pin "8") (pinfunction "8_8") (pintype "passive"))
      (node (ref "LD3") (pin "8") (pinfunction "8_8") (pintype "passive"))
      (node (ref "U2") (pin "14") (pinfunction "OUT3_14") (pintype "passive"))
    )
    (net (code "18") (name "/L1_R4") (class "Default")
      (node (ref "LD1") (pin "12") (pinfunction "12_12") (pintype "passive"))
      (node (ref "LD1") (pin "5") (pinfunction "5_5") (pintype "passive"))
      (node (ref "LD2") (pin "12") (pinfunction "12_12") (pintype "passive"))
      (node (ref "LD2") (pin "5") (pinfunction "5_5") (pintype "passive"))
      (node (ref "LD3") (pin "12") (pinfunction "12_12") (pintype "passive"))
      (node (ref "LD3") (pin "5") (pinfunction "5_5") (pintype "passive"))
      (node (ref "U2") (pin "13") (pinfunction "OUT4_13") (pintype "passive"))
    )
    (net (code "19") (name "/L1_R5") (class "Default")
      (node (ref "LD1") (pin "1") (pinfunction "1_1") (pintype "passive"))
      (node (ref "LD2") (pin "1") (pinfunction "1_1") (pintype "passive"))
      (node (ref "LD3") (pin "1") (pinfunction "1_1") (pintype "passive"))
      (node (ref "U2") (pin "12") (pinfunction "OUT5_12") (pintype "passive"))
    )
    (net (code "20") (name "/L1_R6") (class "Default")
      (node (ref "LD1") (pin "7") (pinfunction "7_7") (pintype "passive"))
      (node (ref "LD2") (pin "7") (pinfunction "7_7") (pintype "passive"))
      (node (ref "LD3") (pin "7") (pinfunction "7_7") (pintype "passive"))
      (node (ref "U2") (pin "11") (pinfunction "OUT6_11") (pintype "passive"))
    )
    (net (code "21") (name "/L1_R7") (class "Default")
      (node (ref "LD1") (pin "2") (pinfunction "2_2") (pintype "passive"))
      (node (ref "LD2") (pin "2") (pinfunction "2_2") (pintype "passive"))
      (node (ref "LD3") (pin "2") (pinfunction "2_2") (pintype "passive"))
      (node (ref "U2") (pin "10") (pinfunction "OUT7_10") (pintype "passive"))
    )
    (net (code "22") (name "/L2_C1") (class "Default")
      (node (ref "LD2") (pin "13") (pinfunction "13_13") (pintype "passive"))
      (node (ref "R20") (pin "2") (pinfunction "2_2") (pintype "passive"))
    )
    (net (code "23") (name "/L2_C2") (class "Default")
      (node (ref "LD2") (pin "3") (pinfunction "3_3") (pintype "passive"))
      (node (ref "R24") (pin "2") (pinfunction "2_2") (pintype "passive"))
    )
    (net (code "24") (name "/L2_C3") (class "Default")
      (node (ref "LD2") (pin "11") (pinfunction "11_11") (pintype "passive"))
      (node (ref "LD2") (pin "4") (pinfunction "4_4") (pintype "passive"))
      (node (ref "R21") (pin "2") (pinfunction "2_2") (pintype "passive"))
    )
    (net (code "25") (name "/L2_C4") (class "Default")
      (node (ref "LD2") (pin "10") (pinfunction "10_10") (pintype "passive"))
      (node (ref "R14") (pin "1") (pinfunction "1_1") (pintype "passive"))
    )
    (net (code "26") (name "/L2_C5") (class "Default")
      (node (ref "LD2") (pin "6") (pinfunction "6_6") (pintype "passive"))
      (node (ref "R17") (pin "1") (pinfunction "1_1") (pintype "passive"))
    )
    (net (code "27") (name "/L3_C1") (class "Default")
      (node (ref "LD3") (pin "13") (pinfunction "13_13") (pintype "passive"))
      (node (ref "R18") (pin "1") (pinfunction "1_1") (pintype "passive"))
    )
    (net (code "28") (name "/L3_C2") (class "Default")
      (node (ref "LD3") (pin "3") (pinfunction "3_3") (pintype "passive"))
      (node (ref "R19") (pin "1") (pinfunction "1_1") (pintype "passive"))
    )
    (net (code "29") (name "/L3_C3") (class "Default")
      (node (ref "LD3") (pin "11") (pinfunction "11_11") (pintype "passive"))
      (node (ref "LD3") (pin "4") (pinfunction "4_4") (pintype "passive"))
      (node (ref "R22") (pin "2") (pinfunction "2_2") (pintype "passive"))
    )
    (net (code "30") (name "/L3_C4") (class "Default")
      (node (ref "LD3") (pin "10") (pinfunction "10_10") (pintype "passive"))
      (node (ref "R25") (pin "2") (pinfunction "2_2") (pintype "passive"))
    )
    (net (code "31") (name "/L3_C5") (class "Default")
      (node (ref "LD3") (pin "6") (pinfunction "6_6") (pintype "passive"))
      (node (ref "R23") (pin "2") (pinfunction "2_2") (pintype "passive"))
    )
    (net (code "32") (name "/LD_RED+") (class "Default")
      (node (ref "D2") (pin "2") (pinfunction "K_2") (pintype "passive"))
      (node (ref "J3") (pin "1") (pinfunction "1_1") (pintype "passive"))
      (node (ref "J3") (pin "2") (pinfunction "2_2") (pintype "passive"))
      (node (ref "J4") (pin "1") (pinfunction "1_1") (pintype "passive"))
      (node (ref "J4") (pin "2") (pinfunction "2_2") (pintype "passive"))
      (node (ref "J5") (pin "1") (pinfunction "1_1") (pintype "passive"))
      (node (ref "J5") (pin "2") (pinfunction "2_2") (pintype "passive"))
      (node (ref "J6") (pin "1") (pinfunction "1_1") (pintype "passive"))
      (node (ref "J6") (pin "2") (pinfunction "2_2") (pintype "passive"))
      (node (ref "LD4") (pin "1") (pinfunction "A_1") (pintype "passive"))
    )
    (net (code "33") (name "/LD_RED-") (class "Default")
      (node (ref "LD4") (pin "2") (pinfunction "K_2") (pintype "passive"))
      (node (ref "R26") (pin "2") (pinfunction "2_2") (pintype "passive"))
      (node (ref "R27") (pin "2") (pinfunction "2_2") (pintype "passive"))
      (node (ref "R28") (pin "2") (pinfunction "2_2") (pintype "passive"))
      (node (ref "R29") (pin "2") (pinfunction "2_2") (pintype "passive"))
    )
    (net (code "34") (name "/MOD+") (class "Default")
      (node (ref "F5") (pin "2") (pinfunction "2_2") (pintype "passive"))
      (node (ref "J7") (pin "2") (pinfunction "2_2") (pintype "passive"))
    )
    (net (code "35") (name "/MOD-") (class "Default")
      (node (ref "F6") (pin "2") (pinfunction "2_2") (pintype "passive"))
      (node (ref "J7") (pin "3") (pinfunction "3_3") (pintype "passive"))
    )
    (net (code "36") (name "/OUT_CTRL2") (class "Default")
      (node (ref "R36") (pin "1") (pinfunction "1_1") (pintype "passive"))
      (node (ref "U6") (pin "15") (pinfunction "OUT2_15") (pintype "passive"))
      (node (ref "U6") (pin "16") (pinfunction "OUT1_16") (pintype "passive"))
    )
    (net (code "37") (name "/OUT_CTRL3") (class "Default")
      (node (ref "R37") (pin "1") (pinfunction "1_1") (pintype "passive"))
      (node (ref "U6") (pin "13") (pinfunction "OUT4_13") (pintype "passive"))
      (node (ref "U6") (pin "14") (pinfunction "OUT3_14") (pintype "passive"))
    )
    (net (code "38") (name "/OUT_CTRL5") (class "Default")
      (node (ref "R34") (pin "2") (pinfunction "2_2") (pintype "passive"))
      (node (ref "U6") (pin "12") (pinfunction "OUT5_12") (pintype "passive"))
    )
    (net (code "39") (name "/OUT_CTRL6") (class "Default")
      (node (ref "R35") (pin "2") (pinfunction "2_2") (pintype "passive"))
      (node (ref "U6") (pin "11") (pinfunction "OUT6_11") (pintype "passive"))
    )
    (net (code "40") (name "/Q1A") (class "Default")
      (node (ref "R13") (pin "1") (pinfunction "1_1") (pintype "passive"))
      (node (ref "U4") (pin "15") (pinfunction "QA_15") (pintype "tri_state"))
    )
    (net (code "41") (name "/Q1B") (class "Default")
      (node (ref "R12") (pin "1") (pinfunction "1_1") (pintype "passive"))
      (node (ref "U4") (pin "1") (pinfunction "QB_1") (pintype "tri_state"))
    )
    (net (code "42") (name "/Q1C") (class "Default")
      (node (ref "R11") (pin "1") (pinfunction "1_1") (pintype "passive"))
      (node (ref "U4") (pin "2") (pinfunction "QC_2") (pintype "tri_state"))
    )
    (net (code "43") (name "/Q1D") (class "Default")
      (node (ref "R10") (pin "1") (pinfunction "1_1") (pintype "passive"))
      (node (ref "U4") (pin "3") (pinfunction "QD_3") (pintype "tri_state"))
    )
    (net (code "44") (name "/Q1E") (class "Default")
      (node (ref "R9") (pin "1") (pinfunction "1_1") (pintype "passive"))
      (node (ref "U4") (pin "4") (pinfunction "QE_4") (pintype "tri_state"))
    )
    (net (code "45") (name "/Q1F") (class "Default")
      (node (ref "R20") (pin "1") (pinfunction "1_1") (pintype "passive"))
      (node (ref "U4") (pin "5") (pinfunction "QF_5") (pintype "tri_state"))
    )
    (net (code "46") (name "/Q1G") (class "Default")
      (node (ref "R24") (pin "1") (pinfunction "1_1") (pintype "passive"))
      (node (ref "U4") (pin "6") (pinfunction "QG_6") (pintype "tri_state"))
    )
    (net (code "47") (name "/Q1H") (class "Default")
      (node (ref "R21") (pin "1") (pinfunction "1_1") (pintype "passive"))
      (node (ref "U4") (pin "7") (pinfunction "QH_7") (pintype "tri_state"))
    )
    (net (code "48") (name "/Q1_CLK") (class "Default")
      (node (ref "U3") (pin "10") (pinfunction "PB6_10") (pintype "passive"))
      (node (ref "U4") (pin "11") (pinfunction "SFTCLK_11") (pintype "passive"))
      (node (ref "U5") (pin "11") (pinfunction "SFTCLK_11") (pintype "passive"))
    )
    (net (code "49") (name "/Q1_LATCH") (class "Default")
      (node (ref "R16") (pin "1") (pinfunction "1_1") (pintype "passive"))
      (node (ref "U3") (pin "11") (pinfunction "PB5_11") (pintype "passive"))
      (node (ref "U4") (pin "12") (pinfunction "LCHCLK_12") (pintype "passive"))
      (node (ref "U5") (pin "12") (pinfunction "LCHCLK_12") (pintype "passive"))
    )
    (net (code "50") (name "/Q1_SDI") (class "Default")
      (node (ref "U3") (pin "9") (pinfunction "PB7_9") (pintype "passive"))
      (node (ref "U4") (pin "14") (pinfunction "SDI_14") (pintype "passive"))
    )
    (net (code "51") (name "/Q2A") (class "Default")
      (node (ref "R14") (pin "2") (pinfunction "2_2") (pintype "passive"))
      (node (ref "U5") (pin "15") (pinfunction "QA_15") (pintype "tri_state"))
    )
    (net (code "52") (name "/Q2B") (class "Default")
      (node (ref "R17") (pin "2") (pinfunction "2_2") (pintype "passive"))
      (node (ref "U5") (pin "1") (pinfunction "QB_1") (pintype "tri_state"))
    )
    (net (code "53") (name "/Q2C") (class "Default")
      (node (ref "R18") (pin "2") (pinfunction "2_2") (pintype "passive"))
      (node (ref "U5") (pin "2") (pinfunction "QC_2") (pintype "tri_state"))
    )
    (net (code "54") (name "/Q2D") (class "Default")
      (node (ref "R19") (pin "2") (pinfunction "2_2") (pintype "passive"))
      (node (ref "U5") (pin "3") (pinfunction "QD_3") (pintype "tri_state"))
    )
    (net (code "55") (name "/Q2E") (class "Default")
      (node (ref "R22") (pin "1") (pinfunction "1_1") (pintype "passive"))
      (node (ref "U5") (pin "4") (pinfunction "QE_4") (pintype "tri_state"))
    )
    (net (code "56") (name "/Q2F") (class "Default")
      (node (ref "R25") (pin "1") (pinfunction "1_1") (pintype "passive"))
      (node (ref "U5") (pin "5") (pinfunction "QF_5") (pintype "tri_state"))
    )
    (net (code "57") (name "/Q2G") (class "Default")
      (node (ref "R23") (pin "1") (pinfunction "1_1") (pintype "passive"))
      (node (ref "U5") (pin "6") (pinfunction "QG_6") (pintype "tri_state"))
    )
    (net (code "58") (name "/Q2H") (class "Default")
      (node (ref "U5") (pin "7") (pinfunction "QH_7") (pintype "tri_state"))
    )
    (net (code "59") (name "/RE") (class "Default")
      (node (ref "R43") (pin "2") (pinfunction "2_2") (pintype "passive"))
      (node (ref "R44") (pin "2") (pinfunction "2_2") (pintype "passive"))
      (node (ref "U7") (pin "2") (pinfunction "RE/_2") (pintype "passive"))
      (node (ref "U8") (pin "2") (pinfunction "RE/_2") (pintype "passive"))
    )
    (net (code "60") (name "/Vcap") (class "Default")
      (node (ref "C11") (pin "1") (pinfunction "1_1") (pintype "passive"))
      (node (ref "U3") (pin "5") (pinfunction "VCAP_5") (pintype "passive"))
    )
    (net (code "61") (name "/uC_BUTTON") (class "Default")
      (node (ref "R48") (pin "1") (pinfunction "1_1") (pintype "passive"))
      (node (ref "U3") (pin "8") (pinfunction "PF4_8") (pintype "passive"))
    )
    (net (code "62") (name "/uC_DE") (class "Default")
      (node (ref "R42") (pin "2") (pinfunction "2_2") (pintype "passive"))
      (node (ref "R44") (pin "1") (pinfunction "1_1") (pintype "passive"))
      (node (ref "U3") (pin "32") (pinfunction "PD7_32") (pintype "passive"))
      (node (ref "U7") (pin "3") (pinfunction "DE_3") (pintype "passive"))
      (node (ref "U8") (pin "3") (pinfunction "DE_3") (pintype "passive"))
    )
    (net (code "63") (name "/uC_NRST") (class "Default")
      (node (ref "C8") (pin "1") (pinfunction "1_1") (pintype "passive"))
      (node (ref "R7") (pin "2") (pinfunction "2_2") (pintype "passive"))
      (node (ref "R8") (pin "2") (pinfunction "2_2") (pintype "passive"))
      (node (ref "U3") (pin "1") (pinfunction "NRST_1") (pintype "passive"))
    )
    (net (code "64") (name "/uC_PA3") (class "Default")
      (node (ref "R3") (pin "2") (pinfunction "2_2") (pintype "passive"))
      (node (ref "U3") (pin "7") (pinfunction "PA3_7") (pintype "passive"))
    )
    (net (code "65") (name "/uC_PD0") (class "Default")
      (node (ref "C20") (pin "2") (pinfunction "2_2") (pintype "passive"))
      (node (ref "R39") (pin "2") (pinfunction "2_2") (pintype "passive"))
      (node (ref "R46") (pin "1") (pinfunction "1_1") (pintype "passive"))
      (node (ref "U3") (pin "25") (pinfunction "PD0_25") (pintype "passive"))
    )
    (net (code "66") (name "/uC_PD2") (class "Default")
      (node (ref "C18") (pin "2") (pinfunction "2_2") (pintype "passive"))
      (node (ref "R31") (pin "1") (pinfunction "1_1") (pintype "passive"))
      (node (ref "R33") (pin "1") (pinfunction "1_1") (pintype "passive"))
      (node (ref "U3") (pin "27") (pinfunction "PD2_27") (pintype "passive"))
    )
    (net (code "67") (name "/uC_PD3") (class "Default")
      (node (ref "C17") (pin "2") (pinfunction "2_2") (pintype "passive"))
      (node (ref "R30") (pin "1") (pinfunction "1_1") (pintype "passive"))
      (node (ref "R32") (pin "1") (pinfunction "1_1") (pintype "passive"))
      (node (ref "U3") (pin "28") (pinfunction "PD3_28") (pintype "passive"))
    )
    (net (code "68") (name "/uC_PE5") (class "Default")
      (node (ref "C19") (pin "2") (pinfunction "2_2") (pintype "passive"))
      (node (ref "R38") (pin "2") (pinfunction "2_2") (pintype "passive"))
      (node (ref "R45") (pin "1") (pinfunction "1_1") (pintype "passive"))
      (node (ref "U3") (pin "17") (pinfunction "PE5_17") (pintype "passive"))
    )
    (net (code "69") (name "/uC_RX") (class "Default")
      (node (ref "C22") (pin "2") (pinfunction "2_2") (pintype "passive"))
      (node (ref "R40") (pin "2") (pinfunction "2_2") (pintype "passive"))
      (node (ref "U3") (pin "31") (pinfunction "PD6/RX_31") (pintype "passive"))
      (node (ref "U7") (pin "1") (pinfunction "RO_1") (pintype "passive"))
      (node (ref "U8") (pin "1") (pinfunction "RO_1") (pintype "passive"))
    )
    (net (code "70") (name "/uC_SWIM") (class "Default")
      (node (ref "R5") (pin "1") (pinfunction "1_1") (pintype "passive"))
      (node (ref "R6") (pin "2") (pinfunction "2_2") (pintype "passive"))
      (node (ref "U3") (pin "26") (pinfunction "PD1/SWIM_26") (pintype "passive"))
    )
    (net (code "71") (name "/uC_TX") (class "Default")
      (node (ref "C21") (pin "2") (pinfunction "2_2") (pintype "passive"))
      (node (ref "R41") (pin "2") (pinfunction "2_2") (pintype "passive"))
      (node (ref "U3") (pin "30") (pinfunction "PD5/TX_30") (pintype "passive"))
      (node (ref "U7") (pin "4") (pinfunction "DI_4") (pintype "passive"))
      (node (ref "U8") (pin "4") (pinfunction "DI_4") (pintype "passive"))
    )
    (net (code "72") (name "5V") (class "Default")
      (node (ref "C12") (pin "2") (pinfunction "2_2") (pintype "passive"))
      (node (ref "C13") (pin "2") (pinfunction "2_2") (pintype "passive"))
      (node (ref "C14") (pin "2") (pinfunction "2_2") (pintype "passive"))
      (node (ref "C15") (pin "2") (pinfunction "2_2") (pintype "passive"))
      (node (ref "C16") (pin "2") (pinfunction "2_2") (pintype "passive"))
      (node (ref "C2") (pin "1") (pinfunction "+_1") (pintype "passive"))
      (node (ref "C24") (pin "1") (pinfunction "1_1") (pintype "passive"))
      (node (ref "C25") (pin "2") (pinfunction "2_2") (pintype "passive"))
      (node (ref "C3") (pin "2") (pinfunction "2_2") (pintype "passive"))
      (node (ref "C4") (pin "1") (pinfunction "1_1") (pintype "passive"))
      (node (ref "J2") (pin "1") (pinfunction "1_1") (pintype "passive"))
      (node (ref "R15") (pin "2") (pinfunction "2_2") (pintype "passive"))
      (node (ref "R16") (pin "2") (pinfunction "2_2") (pintype "passive"))
      (node (ref "R4") (pin "2") (pinfunction "2_2") (pintype "passive"))
      (node (ref "R40") (pin "1") (pinfunction "1_1") (pintype "passive"))
      (node (ref "R41") (pin "1") (pinfunction "1_1") (pintype "passive"))
      (node (ref "R42") (pin "1") (pinfunction "1_1") (pintype "passive"))
      (node (ref "R47") (pin "1") (pinfunction "1_1") (pintype "passive"))
      (node (ref "R6") (pin "1") (pinfunction "1_1") (pintype "passive"))
      (node (ref "R7") (pin "1") (pinfunction "1_1") (pintype "passive"))
      (node (ref "U1") (pin "3") (pinfunction "OUT_3") (pintype "passive"))
      (node (ref "U3") (pin "6") (pinfunction "VDD_6") (pintype "passive"))
      (node (ref "U4") (pin "10") (pinfunction "~{RST}_10") (pintype "passive"))
      (node (ref "U4") (pin "16") (pinfunction "VDD_16") (pintype "power_in"))
      (node (ref "U5") (pin "10") (pinfunction "~{RST}_10") (pintype "passive"))
      (node (ref "U5") (pin "16") (pinfunction "VDD_16") (pintype "power_in"))
      (node (ref "U7") (pin "8") (pinfunction "VCC_8") (pintype "passive"))
      (node (ref "U8") (pin "8") (pinfunction "VCC_8") (pintype "passive"))
    )
    (net (code "73") (name "24V") (class "Default")
      (node (ref "D1") (pin "1") (pinfunction "A_1") (pintype "passive"))
      (node (ref "J7") (pin "1") (pinfunction "1_1") (pintype "passive"))
    )
    (net (code "74") (name "GND") (class "Default")
      (node (ref "C1") (pin "2") (pinfunction "2_2") (pintype "passive"))
      (node (ref "C10") (pin "1") (pinfunction "1_1") (pintype "passive"))
      (node (ref "C11") (pin "2") (pinfunction "2_2") (pintype "passive"))
      (node (ref "C12") (pin "1") (pinfunction "1_1") (pintype "passive"))
      (node (ref "C13") (pin "1") (pinfunction "1_1") (pintype "passive"))
      (node (ref "C14") (pin "1") (pinfunction "1_1") (pintype "passive"))
      (node (ref "C15") (pin "1") (pinfunction "1_1") (pintype "passive"))
      (node (ref "C16") (pin "1") (pinfunction "1_1") (pintype "passive"))
      (node (ref "C17") (pin "1") (pinfunction "1_1") (pintype "passive"))
      (node (ref "C18") (pin "1") (pinfunction "1_1") (pintype "passive"))
      (node (ref "C19") (pin "1") (pinfunction "1_1") (pintype "passive"))
      (node (ref "C2") (pin "2") (pinfunction "-_2") (pintype "passive"))
      (node (ref "C20") (pin "1") (pinfunction "1_1") (pintype "passive"))
      (node (ref "C21") (pin "1") (pinfunction "1_1") (pintype "passive"))
      (node (ref "C22") (pin "1") (pinfunction "1_1") (pintype "passive"))
      (node (ref "C23") (pin "2") (pinfunction "2_2") (pintype "passive"))
      (node (ref "C24") (pin "2") (pinfunction "2_2") (pintype "passive"))
      (node (ref "C25") (pin "1") (pinfunction "1_1") (pintype "passive"))
      (node (ref "C3") (pin "1") (pinfunction "1_1") (pintype "passive"))
      (node (ref "C4") (pin "2") (pinfunction "2_2") (pintype "passive"))
      (node (ref "C5") (pin "2") (pinfunction "-_2") (pintype "passive"))
      (node (ref "C6") (pin "1") (pinfunction "1_1") (pintype "passive"))
      (node (ref "C7") (pin "2") (pinfunction "2_2") (pintype "passive"))
      (node (ref "C8") (pin "2") (pinfunction "2_2") (pintype "passive"))
      (node (ref "C9") (pin "1") (pinfunction "1_1") (pintype "passive"))
      (node (ref "J2") (pin "4") (pinfunction "4_4") (pintype "passive"))
      (node (ref "J7") (pin "4") (pinfunction "4_4") (pintype "passive"))
      (node (ref "R1") (pin "1") (pinfunction "1_1") (pintype "passive"))
      (node (ref "R32") (pin "2") (pinfunction "2_2") (pintype "passive"))
      (node (ref "R33") (pin "2") (pinfunction "2_2") (pintype "passive"))
      (node (ref "R43") (pin "1") (pinfunction "1_1") (pintype "passive"))
      (node (ref "R45") (pin "2") (pinfunction "2_2") (pintype "passive"))
      (node (ref "R46") (pin "2") (pinfunction "2_2") (pintype "passive"))
      (node (ref "R49") (pin "1") (pinfunction "1_1") (pintype "passive"))
      (node (ref "TZ1") (pin "2") (pinfunction "2_2") (pintype "passive"))
      (node (ref "TZ2") (pin "2") (pinfunction "2_2") (pintype "passive"))
      (node (ref "U1") (pin "2") (pinfunction "GND_2") (pintype "passive"))
      (node (ref "U2") (pin "8") (pinfunction "GND_8") (pintype "passive"))
      (node (ref "U3") (pin "4") (pinfunction "VSS_4") (pintype "passive"))
      (node (ref "U4") (pin "13") (pinfunction "~{OE}_13") (pintype "passive"))
      (node (ref "U4") (pin "8") (pinfunction "GND_8") (pintype "power_in"))
      (node (ref "U5") (pin "13") (pinfunction "~{OE}_13") (pintype "passive"))
      (node (ref "U5") (pin "8") (pinfunction "GND_8") (pintype "power_in"))
      (node (ref "U6") (pin "8") (pinfunction "GND_8") (pintype "passive"))
      (node (ref "U7") (pin "5") (pinfunction "GND_5") (pintype "passive"))
      (node (ref "U8") (pin "5") (pinfunction "GND_5") (pintype "passive"))
    )
    (net (code "75") (name "Net-(C1-Pad1)") (class "Default")
      (node (ref "C1") (pin "1") (pinfunction "1_1") (pintype "passive"))
      (node (ref "J1") (pin "2") (pinfunction "2_2") (pintype "passive"))
      (node (ref "R1") (pin "2") (pinfunction "2_2") (pintype "passive"))
      (node (ref "R3") (pin "1") (pinfunction "1_1") (pintype "passive"))
    )
    (net (code "76") (name "Net-(C5-+)") (class "Default")
      (node (ref "C5") (pin "1") (pinfunction "+_1") (pintype "passive"))
      (node (ref "C6") (pin "2") (pinfunction "2_2") (pintype "passive"))
      (node (ref "C7") (pin "1") (pinfunction "1_1") (pintype "passive"))
      (node (ref "R2") (pin "2") (pinfunction "2_2") (pintype "passive"))
      (node (ref "U1") (pin "1") (pinfunction "IN_1") (pintype "passive"))
    )
    (net (code "77") (name "Net-(C23-Pad1)") (class "Default")
      (node (ref "C23") (pin "1") (pinfunction "1_1") (pintype "passive"))
      (node (ref "R48") (pin "2") (pinfunction "2_2") (pintype "passive"))
      (node (ref "R49") (pin "2") (pinfunction "2_2") (pintype "passive"))
      (node (ref "SW1") (pin "2") (pinfunction "2_2") (pintype "passive"))
    )
    (net (code "78") (name "Net-(C26-Pad1)") (class "Default")
      (node (ref "C26") (pin "1") (pinfunction "1_1") (pintype "passive"))
      (node (ref "F5") (pin "1") (pinfunction "1_1") (pintype "passive"))
      (node (ref "FB1") (pin "2") (pinfunction "2_2") (pintype "passive"))
      (node (ref "TZ1") (pin "1") (pinfunction "1_1") (pintype "passive"))
    )
    (net (code "79") (name "Net-(C26-Pad2)") (class "Default")
      (node (ref "C26") (pin "2") (pinfunction "2_2") (pintype "passive"))
      (node (ref "F6") (pin "1") (pinfunction "1_1") (pintype "passive"))
      (node (ref "FB2") (pin "2") (pinfunction "2_2") (pintype "passive"))
      (node (ref "TZ2") (pin "1") (pinfunction "1_1") (pintype "passive"))
    )
    (net (code "80") (name "Net-(D1-K)") (class "Default")
      (node (ref "D1") (pin "2") (pinfunction "K_2") (pintype "passive"))
      (node (ref "D2") (pin "1") (pinfunction "A_1") (pintype "passive"))
      (node (ref "R2") (pin "1") (pinfunction "1_1") (pintype "passive"))
    )
    (net (code "81") (name "Net-(J1-Pad3)") (class "Default")
      (node (ref "J1") (pin "3") (pinfunction "3_3") (pintype "passive"))
      (node (ref "R4") (pin "1") (pinfunction "1_1") (pintype "passive"))
    )
    (net (code "82") (name "Net-(J2-Pad2)") (class "Default")
      (node (ref "J2") (pin "2") (pinfunction "2_2") (pintype "passive"))
      (node (ref "R5") (pin "2") (pinfunction "2_2") (pintype "passive"))
    )
    (net (code "83") (name "Net-(J2-Pad3)") (class "Default")
      (node (ref "J2") (pin "3") (pinfunction "3_3") (pintype "passive"))
      (node (ref "R8") (pin "1") (pinfunction "1_1") (pintype "passive"))
    )
    (net (code "84") (name "Net-(J3-Pad3)") (class "Default")
      (node (ref "J3") (pin "3") (pinfunction "3_3") (pintype "passive"))
      (node (ref "R30") (pin "2") (pinfunction "2_2") (pintype "passive"))
    )
    (net (code "85") (name "Net-(J3-Pad4)") (class "Default")
      (node (ref "J3") (pin "4") (pinfunction "4_4") (pintype "passive"))
      (node (ref "R34") (pin "1") (pinfunction "1_1") (pintype "passive"))
    )
    (net (code "86") (name "Net-(J4-Pad3)") (class "Default")
      (node (ref "J4") (pin "3") (pinfunction "3_3") (pintype "passive"))
      (node (ref "R31") (pin "2") (pinfunction "2_2") (pintype "passive"))
    )
    (net (code "87") (name "Net-(J4-Pad4)") (class "Default")
      (node (ref "J4") (pin "4") (pinfunction "4_4") (pintype "passive"))
      (node (ref "R35") (pin "1") (pinfunction "1_1") (pintype "passive"))
    )
    (net (code "88") (name "Net-(J5-Pad3)") (class "Default")
      (node (ref "J5") (pin "3") (pinfunction "3_3") (pintype "passive"))
      (node (ref "R38") (pin "1") (pinfunction "1_1") (pintype "passive"))
    )
    (net (code "89") (name "Net-(J5-Pad4)") (class "Default")
      (node (ref "J5") (pin "4") (pinfunction "4_4") (pintype "passive"))
      (node (ref "R36") (pin "2") (pinfunction "2_2") (pintype "passive"))
    )
    (net (code "90") (name "Net-(J6-Pad3)") (class "Default")
      (node (ref "J6") (pin "3") (pinfunction "3_3") (pintype "passive"))
      (node (ref "R39") (pin "1") (pinfunction "1_1") (pintype "passive"))
    )
    (net (code "91") (name "Net-(J6-Pad4)") (class "Default")
      (node (ref "J6") (pin "4") (pinfunction "4_4") (pintype "passive"))
      (node (ref "R37") (pin "2") (pinfunction "2_2") (pintype "passive"))
    )
    (net (code "92") (name "Net-(R47-Pad2)") (class "Default")
      (node (ref "R47") (pin "2") (pinfunction "2_2") (pintype "passive"))
      (node (ref "SW1") (pin "4") (pinfunction "4_4") (pintype "passive"))
    )
    (net (code "93") (name "Net-(U3-OSCIN{slash}PA1)") (class "Default")
      (node (ref "C9") (pin "2") (pinfunction "2_2") (pintype "passive"))
      (node (ref "U3") (pin "2") (pinfunction "OSCIN/PA1_2") (pintype "passive"))
      (node (ref "X1") (pin "2") (pinfunction "2_2") (pintype "passive"))
    )
    (net (code "94") (name "Net-(U3-OSCOUT{slash}PA2)") (class "Default")
      (node (ref "C10") (pin "2") (pinfunction "2_2") (pintype "passive"))
      (node (ref "U3") (pin "3") (pinfunction "OSCOUT/PA2_3") (pintype "passive"))
      (node (ref "X1") (pin "1") (pinfunction "1_1") (pintype "passive"))
    )
    (net (code "95") (name "Net-(U3-PB0)") (class "Default")
      (node (ref "U3") (pin "16") (pinfunction "PB0_16") (pintype "passive"))
      (node (ref "U6") (pin "1") (pinfunction "IN1_1") (pintype "passive"))
      (node (ref "U6") (pin "2") (pinfunction "IN2_2") (pintype "passive"))
    )
    (net (code "96") (name "Net-(U3-PB1)") (class "Default")
      (node (ref "U3") (pin "15") (pinfunction "PB1_15") (pintype "passive"))
      (node (ref "U6") (pin "3") (pinfunction "IN3_3") (pintype "passive"))
      (node (ref "U6") (pin "4") (pinfunction "IN4_4") (pintype "passive"))
    )
    (net (code "97") (name "Net-(U3-PB2)") (class "Default")
      (node (ref "U3") (pin "14") (pinfunction "PB2_14") (pintype "passive"))
      (node (ref "U6") (pin "5") (pinfunction "IN5_5") (pintype "passive"))
    )
    (net (code "98") (name "Net-(U3-PB3)") (class "Default")
      (node (ref "U3") (pin "13") (pinfunction "PB3_13") (pintype "passive"))
      (node (ref "U6") (pin "6") (pinfunction "IN6_6") (pintype "passive"))
    )
    (net (code "99") (name "Net-(U3-PB4)") (class "Default")
      (node (ref "R15") (pin "1") (pinfunction "1_1") (pintype "passive"))
      (node (ref "U3") (pin "12") (pinfunction "PB4_12") (pintype "passive"))
      (node (ref "U6") (pin "7") (pinfunction "IN7_7") (pintype "passive"))
    )
    (net (code "100") (name "Net-(U4-SDO)") (class "Default")
      (node (ref "U4") (pin "9") (pinfunction "SDO_9") (pintype "passive"))
      (node (ref "U5") (pin "14") (pinfunction "SDI_14") (pintype "passive"))
    )
    (net (code "101") (name "Net-(U6-OUT7)") (class "Default")
      (node (ref "R26") (pin "1") (pinfunction "1_1") (pintype "passive"))
      (node (ref "R27") (pin "1") (pinfunction "1_1") (pintype "passive"))
      (node (ref "R28") (pin "1") (pinfunction "1_1") (pintype "passive"))
      (node (ref "R29") (pin "1") (pinfunction "1_1") (pintype "passive"))
      (node (ref "U6") (pin "10") (pinfunction "OUT7_10") (pintype "passive"))
    )
    (net (code "102") (name "unconnected-(J1-Pad1)") (class "Default")
      (node (ref "J1") (pin "1") (pinfunction "1_1") (pintype "passive+no_connect"))
    )
    (net (code "103") (name "unconnected-(SW1-Pad1)") (class "Default")
      (node (ref "SW1") (pin "1") (pinfunction "1_1") (pintype "passive"))
    )
    (net (code "104") (name "unconnected-(SW1-Pad3)") (class "Default")
      (node (ref "SW1") (pin "3") (pinfunction "3_3") (pintype "passive"))
    )
    (net (code "105") (name "unconnected-(U2-COM-Pad9)") (class "Default")
      (node (ref "U2") (pin "9") (pinfunction "COM_9") (pintype "passive+no_connect"))
    )
    (net (code "106") (name "unconnected-(U3-PD4-Pad29)") (class "Default")
      (node (ref "U3") (pin "29") (pinfunction "PD4_29") (pintype "passive+no_connect"))
    )
    (net (code "107") (name "unconnected-(U5-SDO-Pad9)") (class "Default")
      (node (ref "U5") (pin "9") (pinfunction "SDO_9") (pintype "passive+no_connect"))
    )
    (net (code "108") (name "unconnected-(U6-COM-Pad9)") (class "Default")
      (node (ref "U6") (pin "9") (pinfunction "COM_9") (pintype "passive+no_connect"))
    )
  )
)
